# sch_easyeda.net
KiCad netlist of a schematic drawn in EasyEDA
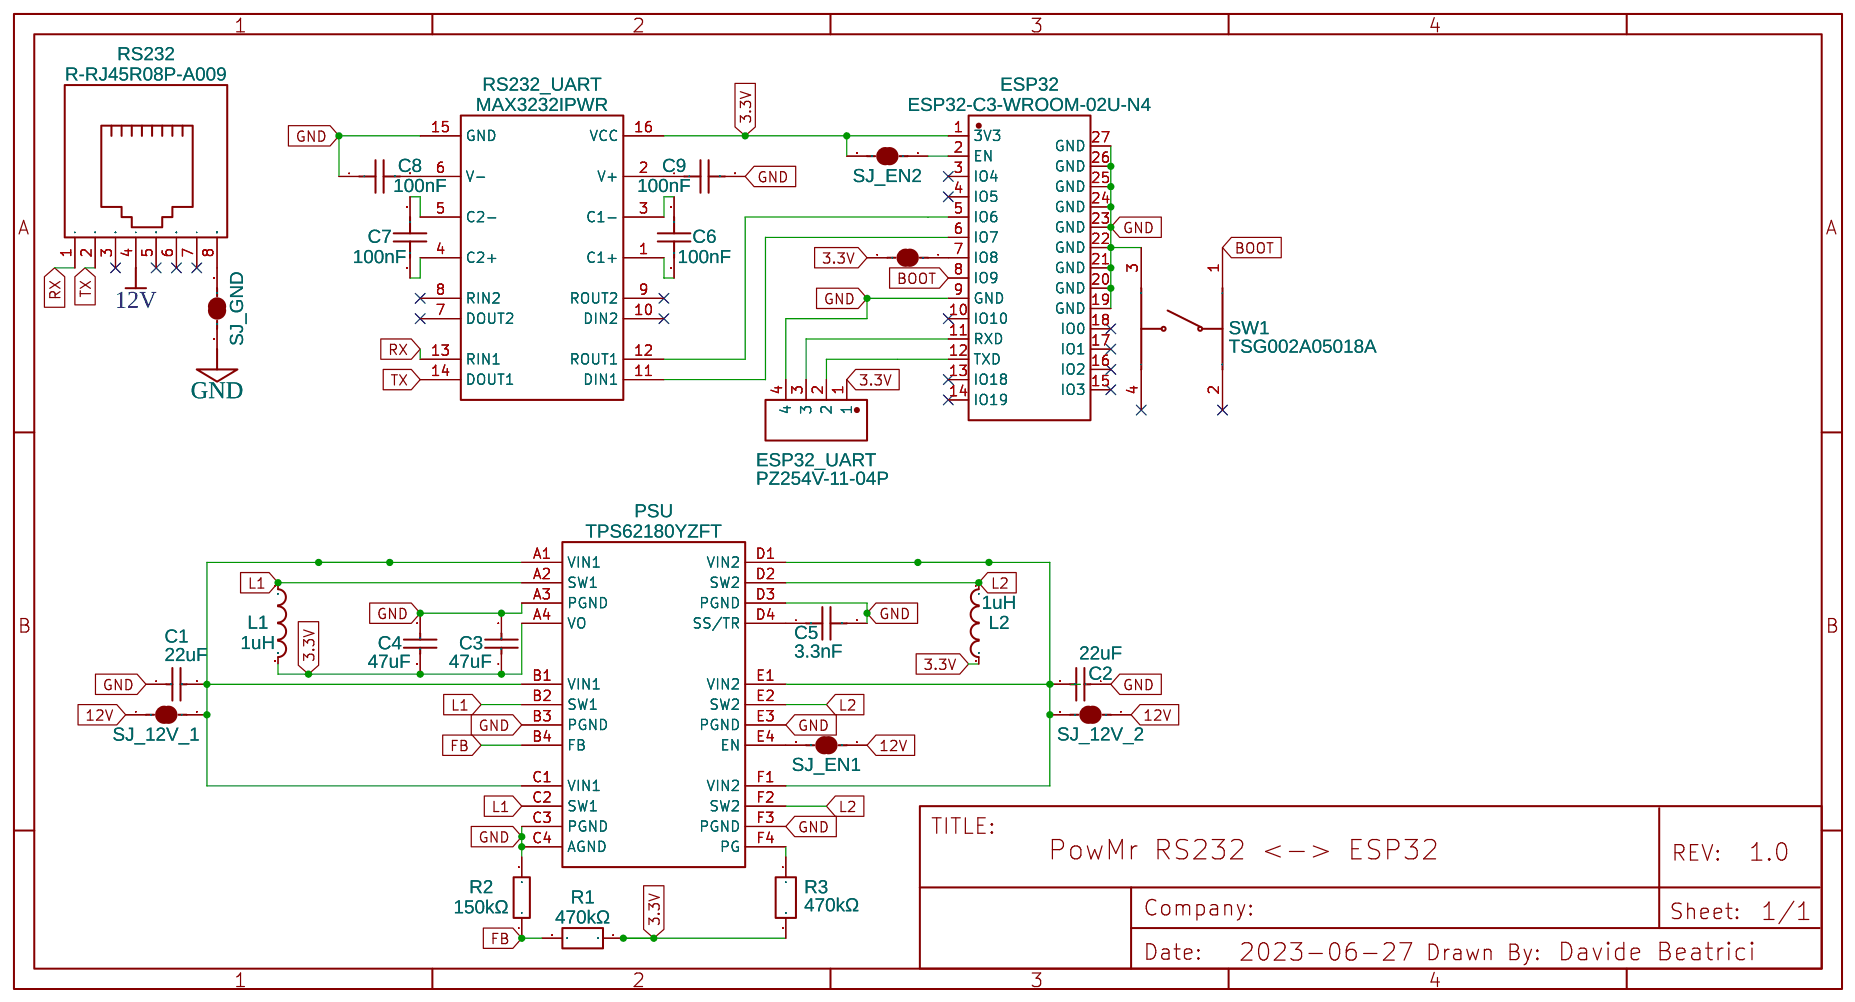
[diagram p0: schematic sheet]

(export (version "E")
  (design (tool "Eeschema 10.0.6"))
  (components
    (comp (ref "C1")
      (value "22uF")
      (fields
        (field (name "BOM_Manufacturer Part") "GRM21BR61E226ME44L")
        (field (name "BOM_Supplier Part") "C86816")
      )
      (libsource (lib "") (part "GRM21BR61E226ME44L"))
    )
    (comp (ref "C2")
      (value "22uF")
      (fields
        (field (name "BOM_Manufacturer Part") "GRM21BR61E226ME44L")
        (field (name "BOM_Supplier Part") "C86816")
      )
      (libsource (lib "") (part "GRM21BR61E226ME44L_1"))
    )
    (comp (ref "C3")
      (value "47uF")
      (fields
        (field (name "BOM_Manufacturer Part") "GRM21BR60J476ME15L")
        (field (name "BOM_Supplier Part") "C77072")
      )
      (libsource (lib "") (part "GRM21BR60J476ME15L"))
    )
    (comp (ref "C4")
      (value "47uF")
      (fields
        (field (name "BOM_Manufacturer Part") "GRM21BR60J476ME15L")
        (field (name "BOM_Supplier Part") "C77072")
      )
      (libsource (lib "") (part "GRM21BR60J476ME15L"))
    )
    (comp (ref "C5")
      (value "3.3nF")
      (fields
        (field (name "BOM_Manufacturer Part") "GRM155R71H332KA01D")
        (field (name "BOM_Supplier Part") "C85963")
      )
      (libsource (lib "") (part "GRM155R71H332KA01D"))
    )
    (comp (ref "C6")
      (value "100nF")
      (fields
        (field (name "BOM_Manufacturer Part") "GRM155R71C104KA88D")
        (field (name "BOM_Supplier Part") "C71629")
      )
      (libsource (lib "") (part "GRM155R71C104KA88D_1"))
    )
    (comp (ref "C7")
      (value "100nF")
      (fields
        (field (name "BOM_Manufacturer Part") "GRM155R71C104KA88D")
        (field (name "BOM_Supplier Part") "C71629")
      )
      (libsource (lib "") (part "GRM155R71C104KA88D_1"))
    )
    (comp (ref "C8")
      (value "100nF")
      (fields
        (field (name "BOM_Manufacturer Part") "GRM155R71C104KA88D")
        (field (name "BOM_Supplier Part") "C71629")
      )
      (libsource (lib "") (part "GRM155R71C104KA88D"))
    )
    (comp (ref "C9")
      (value "100nF")
      (fields
        (field (name "BOM_Manufacturer Part") "GRM155R71C104KA88D")
        (field (name "BOM_Supplier Part") "C71629")
      )
      (libsource (lib "") (part "GRM155R71C104KA88D"))
    )
    (comp (ref "ESP32")
      (value "ESP32-C3-WROOM-02U-N4")
      (fields (field (name "BOM_Supplier Part") "C2926676"))
      (libsource (lib "") (part "ESP32-C3-WROOM-02U-N4"))
    )
    (comp (ref "ESP32_UART")
      (value "PZ254V-11-04P")
      (fields (field (name "BOM_Supplier Part") "C492403"))
      (libsource (lib "") (part "PZ254V-11-04P"))
    )
    (comp (ref "L1")
      (value "1uH")
      (fields
        (field (name "BOM_Manufacturer Part") "DFE252012F-1R0M=P2")
        (field (name "BOM_Supplier Part") "C435392")
      )
      (libsource (lib "") (part "DFE252012F-1R0M=P2_1"))
    )
    (comp (ref "L2")
      (value "1uH")
      (fields
        (field (name "BOM_Manufacturer Part") "DFE252012F-1R0M=P2")
        (field (name "BOM_Supplier Part") "C435392")
      )
      (libsource (lib "") (part "DFE252012F-1R0M=P2"))
    )
    (comp (ref "PSU")
      (value "TPS62180YZFT")
      (fields (field (name "BOM_Supplier Part") "C73980"))
      (libsource (lib "") (part "TPS62180YZFT"))
    )
    (comp (ref "R1")
      (value "470kΩ")
      (fields
        (field (name "BOM_Manufacturer Part") "CRCW0402470KFKED")
        (field (name "BOM_Supplier Part") "C482181")
      )
      (libsource (lib "") (part "CRCW0402470KFKED"))
    )
    (comp (ref "R2")
      (value "150kΩ")
      (fields
        (field (name "BOM_Manufacturer Part") "0402WGF1503TCE")
        (field (name "BOM_Supplier Part") "C25755")
      )
      (libsource (lib "") (part "0402WGF1503TCE"))
    )
    (comp (ref "R3")
      (value "470kΩ")
      (fields
        (field (name "BOM_Manufacturer Part") "CRCW0402470KFKED")
        (field (name "BOM_Supplier Part") "C482181")
      )
      (libsource (lib "") (part "CRCW0402470KFKED_1"))
    )
    (comp (ref "RS232")
      (value "R-RJ45R08P-A009")
      (fields (field (name "BOM_Supplier Part") "C2902700"))
      (libsource (lib "") (part "R-RJ45R08P-A009"))
    )
    (comp (ref "RS232_UART")
      (value "MAX3232IPWR")
      (fields (field (name "BOM_Supplier Part") "C113205"))
      (libsource (lib "") (part "MAX3232IPWR"))
    )
    (comp (ref "SJ_12V_1") (value "SJ_12V_1") (libsource (lib "") (part "SOLDERJUMPERNC2_3")))
    (comp (ref "SJ_12V_2") (value "SJ_12V_2") (libsource (lib "") (part "SOLDERJUMPERNC2_2")))
    (comp (ref "SJ_EN1") (value "SJ_EN1") (libsource (lib "") (part "SOLDERJUMPERNC2_1")))
    (comp (ref "SJ_EN2") (value "SJ_EN2") (libsource (lib "") (part "SOLDERJUMPERNC2_1")))
    (comp (ref "SJ_GND") (value "SJ_GND") (libsource (lib "") (part "SOLDERJUMPERNC2_4")))
    (comp (ref "SJ_IO8") (value "SJ_IO8") (libsource (lib "") (part "SOLDERJUMPERNC2")))
    (comp (ref "SW1")
      (value "TSG002A05018A")
      (fields (field (name "BOM_Supplier Part") "C2888616"))
      (libsource (lib "") (part "TSG002A05018A"))
    )
  )
  (nets
    (net (code "1") (name "3.3V") (class "Default")
      (node (ref "C3") (pin "1") (pinfunction "1_1") (pintype "input"))
      (node (ref "C4") (pin "1") (pinfunction "1_1") (pintype "input"))
      (node (ref "ESP32") (pin "1") (pinfunction "3V3_1") (pintype "unspecified"))
      (node (ref "ESP32_UART") (pin "1") (pinfunction "1_1") (pintype "unspecified"))
      (node (ref "L1") (pin "2") (pinfunction "2_2") (pintype "unspecified"))
      (node (ref "L2") (pin "2") (pinfunction "2_2") (pintype "unspecified"))
      (node (ref "PSU") (pin "A4") (pinfunction "VO_A4") (pintype "unspecified"))
      (node (ref "R1") (pin "1") (pinfunction "1_1") (pintype "unspecified"))
      (node (ref "R3") (pin "2") (pinfunction "2_2") (pintype "unspecified"))
      (node (ref "RS232_UART") (pin "16") (pinfunction "VCC_16") (pintype "passive"))
      (node (ref "SJ_EN2") (pin "2") (pinfunction "2_2") (pintype "unspecified"))
      (node (ref "SJ_IO8") (pin "2") (pinfunction "2_2") (pintype "unspecified"))
    )
    (net (code "2") (name "12V") (class "Default")
      (node (ref "RS232") (pin "4") (pinfunction "4_4") (pintype "unspecified"))
      (node (ref "SJ_12V_1") (pin "1") (pinfunction "1_1") (pintype "unspecified"))
      (node (ref "SJ_12V_2") (pin "1") (pinfunction "1_1") (pintype "unspecified"))
      (node (ref "SJ_EN1") (pin "1") (pinfunction "1_1") (pintype "unspecified"))
    )
    (net (code "3") (name "BOOT") (class "Default")
      (node (ref "ESP32") (pin "8") (pinfunction "IO9_8") (pintype "unspecified"))
      (node (ref "SW1") (pin "1") (pinfunction "1_1") (pintype "unspecified"))
    )
    (net (code "4") (name "FB") (class "Default")
      (node (ref "PSU") (pin "B4") (pinfunction "FB_B4") (pintype "unspecified"))
      (node (ref "R1") (pin "2") (pinfunction "2_2") (pintype "unspecified"))
      (node (ref "R2") (pin "1") (pinfunction "1_1") (pintype "input"))
    )
    (net (code "5") (name "GND") (class "Default")
      (node (ref "C1") (pin "1") (pinfunction "1_1") (pintype "input"))
      (node (ref "C2") (pin "1") (pinfunction "1_1") (pintype "input"))
      (node (ref "C3") (pin "2") (pinfunction "2_2") (pintype "input"))
      (node (ref "C4") (pin "2") (pinfunction "2_2") (pintype "input"))
      (node (ref "C5") (pin "2") (pinfunction "2_2") (pintype "unspecified"))
      (node (ref "C8") (pin "1") (pinfunction "1_1") (pintype "unspecified"))
      (node (ref "C9") (pin "2") (pinfunction "2_2") (pintype "unspecified"))
      (node (ref "ESP32") (pin "19") (pinfunction "GND_19") (pintype "unspecified"))
      (node (ref "ESP32") (pin "20") (pinfunction "GND_20") (pintype "unspecified"))
      (node (ref "ESP32") (pin "21") (pinfunction "GND_21") (pintype "unspecified"))
      (node (ref "ESP32") (pin "22") (pinfunction "GND_22") (pintype "unspecified"))
      (node (ref "ESP32") (pin "23") (pinfunction "GND_23") (pintype "unspecified"))
      (node (ref "ESP32") (pin "24") (pinfunction "GND_24") (pintype "unspecified"))
      (node (ref "ESP32") (pin "25") (pinfunction "GND_25") (pintype "unspecified"))
      (node (ref "ESP32") (pin "26") (pinfunction "GND_26") (pintype "unspecified"))
      (node (ref "ESP32") (pin "27") (pinfunction "GND_27") (pintype "unspecified"))
      (node (ref "ESP32") (pin "9") (pinfunction "GND_9") (pintype "unspecified"))
      (node (ref "ESP32_UART") (pin "4") (pinfunction "4_4") (pintype "unspecified"))
      (node (ref "PSU") (pin "A3") (pinfunction "PGND_A3") (pintype "unspecified"))
      (node (ref "PSU") (pin "B3") (pinfunction "PGND_B3") (pintype "unspecified"))
      (node (ref "PSU") (pin "C3") (pinfunction "PGND_C3") (pintype "unspecified"))
      (node (ref "PSU") (pin "C4") (pinfunction "AGND_C4") (pintype "unspecified"))
      (node (ref "PSU") (pin "D3") (pinfunction "PGND_D3") (pintype "unspecified"))
      (node (ref "PSU") (pin "E3") (pinfunction "PGND_E3") (pintype "unspecified"))
      (node (ref "PSU") (pin "F3") (pinfunction "PGND_F3") (pintype "unspecified"))
      (node (ref "R2") (pin "2") (pinfunction "2_2") (pintype "input"))
      (node (ref "RS232_UART") (pin "15") (pinfunction "GND_15") (pintype "passive"))
      (node (ref "SJ_GND") (pin "1") (pinfunction "1_1") (pintype "unspecified"))
      (node (ref "SW1") (pin "3") (pinfunction "3_3") (pintype "unspecified"))
    )
    (net (code "6") (name "L1") (class "Default")
      (node (ref "L1") (pin "1") (pinfunction "1_1") (pintype "unspecified"))
      (node (ref "PSU") (pin "A2") (pinfunction "SW1_A2") (pintype "unspecified"))
      (node (ref "PSU") (pin "B2") (pinfunction "SW1_B2") (pintype "unspecified"))
      (node (ref "PSU") (pin "C2") (pinfunction "SW1_C2") (pintype "unspecified"))
    )
    (net (code "7") (name "L2") (class "Default")
      (node (ref "L2") (pin "1") (pinfunction "1_1") (pintype "unspecified"))
      (node (ref "PSU") (pin "D2") (pinfunction "SW2_D2") (pintype "unspecified"))
      (node (ref "PSU") (pin "E2") (pinfunction "SW2_E2") (pintype "unspecified"))
      (node (ref "PSU") (pin "F2") (pinfunction "SW2_F2") (pintype "unspecified"))
    )
    (net (code "8") (name "Net-(C1-Pad2)") (class "Default")
      (node (ref "C1") (pin "2") (pinfunction "2_2") (pintype "input"))
      (node (ref "PSU") (pin "A1") (pinfunction "VIN1_A1") (pintype "unspecified"))
      (node (ref "PSU") (pin "B1") (pinfunction "VIN1_B1") (pintype "unspecified"))
      (node (ref "PSU") (pin "C1") (pinfunction "VIN1_C1") (pintype "unspecified"))
      (node (ref "SJ_12V_1") (pin "2") (pinfunction "2_2") (pintype "unspecified"))
    )
    (net (code "9") (name "Net-(C2-Pad2)") (class "Default")
      (node (ref "C2") (pin "2") (pinfunction "2_2") (pintype "input"))
      (node (ref "PSU") (pin "D1") (pinfunction "VIN2_D1") (pintype "unspecified"))
      (node (ref "PSU") (pin "E1") (pinfunction "VIN2_E1") (pintype "unspecified"))
      (node (ref "PSU") (pin "F1") (pinfunction "VIN2_F1") (pintype "unspecified"))
      (node (ref "SJ_12V_2") (pin "2") (pinfunction "2_2") (pintype "unspecified"))
    )
    (net (code "10") (name "Net-(ESP32-EN)") (class "Default")
      (node (ref "ESP32") (pin "2") (pinfunction "EN_2") (pintype "unspecified"))
      (node (ref "SJ_EN2") (pin "1") (pinfunction "1_1") (pintype "unspecified"))
    )
    (net (code "11") (name "Net-(ESP32-IO6)") (class "Default")
      (node (ref "ESP32") (pin "5") (pinfunction "IO6_5") (pintype "unspecified"))
      (node (ref "RS232_UART") (pin "12") (pinfunction "ROUT1_12") (pintype "output"))
    )
    (net (code "12") (name "Net-(ESP32-IO7)") (class "Default")
      (node (ref "ESP32") (pin "6") (pinfunction "IO7_6") (pintype "unspecified"))
      (node (ref "RS232_UART") (pin "11") (pinfunction "DIN1_11") (pintype "unspecified"))
    )
    (net (code "13") (name "Net-(ESP32-IO8)") (class "Default")
      (node (ref "ESP32") (pin "7") (pinfunction "IO8_7") (pintype "unspecified"))
      (node (ref "SJ_IO8") (pin "1") (pinfunction "1_1") (pintype "unspecified"))
    )
    (net (code "14") (name "Net-(ESP32-RXD)") (class "Default")
      (node (ref "ESP32") (pin "11") (pinfunction "RXD_11") (pintype "unspecified"))
      (node (ref "ESP32_UART") (pin "3") (pinfunction "3_3") (pintype "unspecified"))
    )
    (net (code "15") (name "Net-(ESP32-TXD)") (class "Default")
      (node (ref "ESP32") (pin "12") (pinfunction "TXD_12") (pintype "unspecified"))
      (node (ref "ESP32_UART") (pin "2") (pinfunction "2_2") (pintype "unspecified"))
    )
    (net (code "16") (name "Net-(PSU-EN)") (class "Default")
      (node (ref "PSU") (pin "E4") (pinfunction "EN_E4") (pintype "unspecified"))
      (node (ref "SJ_EN1") (pin "2") (pinfunction "2_2") (pintype "unspecified"))
    )
    (net (code "17") (name "Net-(PSU-PG)") (class "Default")
      (node (ref "PSU") (pin "F4") (pinfunction "PG_F4") (pintype "unspecified"))
      (node (ref "R3") (pin "1") (pinfunction "1_1") (pintype "unspecified"))
    )
    (net (code "18") (name "Net-(PSU-SS{slash}TR)") (class "Default")
      (node (ref "C5") (pin "1") (pinfunction "1_1") (pintype "unspecified"))
      (node (ref "PSU") (pin "D4") (pinfunction "SS/TR_D4") (pintype "unspecified"))
    )
    (net (code "19") (name "Net-(RS232-Pad8)") (class "Default")
      (node (ref "RS232") (pin "8") (pinfunction "8_8") (pintype "unspecified"))
      (node (ref "SJ_GND") (pin "2") (pinfunction "2_2") (pintype "unspecified"))
    )
    (net (code "20") (name "Net-(RS232_UART-C1+)") (class "Default")
      (node (ref "C6") (pin "1") (pinfunction "1_1") (pintype "unspecified"))
      (node (ref "RS232_UART") (pin "1") (pinfunction "C1+_1") (pintype "unspecified"))
    )
    (net (code "21") (name "Net-(RS232_UART-C1-)") (class "Default")
      (node (ref "C6") (pin "2") (pinfunction "2_2") (pintype "unspecified"))
      (node (ref "RS232_UART") (pin "3") (pinfunction "C1-_3") (pintype "unspecified"))
    )
    (net (code "22") (name "Net-(RS232_UART-C2+)") (class "Default")
      (node (ref "C7") (pin "1") (pinfunction "1_1") (pintype "unspecified"))
      (node (ref "RS232_UART") (pin "4") (pinfunction "C2+_4") (pintype "unspecified"))
    )
    (net (code "23") (name "Net-(RS232_UART-C2-)") (class "Default")
      (node (ref "C7") (pin "2") (pinfunction "2_2") (pintype "unspecified"))
      (node (ref "RS232_UART") (pin "5") (pinfunction "C2-_5") (pintype "unspecified"))
    )
    (net (code "24") (name "Net-(RS232_UART-V+)") (class "Default")
      (node (ref "C9") (pin "1") (pinfunction "1_1") (pintype "unspecified"))
      (node (ref "RS232_UART") (pin "2") (pinfunction "V+_2") (pintype "passive"))
    )
    (net (code "25") (name "Net-(RS232_UART-V-)") (class "Default")
      (node (ref "C8") (pin "2") (pinfunction "2_2") (pintype "unspecified"))
      (node (ref "RS232_UART") (pin "6") (pinfunction "V-_6") (pintype "passive"))
    )
    (net (code "26") (name "RX") (class "Default")
      (node (ref "RS232") (pin "1") (pinfunction "1_1") (pintype "unspecified"))
      (node (ref "RS232_UART") (pin "13") (pinfunction "RIN1_13") (pintype "unspecified"))
    )
    (net (code "27") (name "TX") (class "Default")
      (node (ref "RS232") (pin "2") (pinfunction "2_2") (pintype "unspecified"))
      (node (ref "RS232_UART") (pin "14") (pinfunction "DOUT1_14") (pintype "output"))
    )
    (net (code "28") (name "unconnected-(ESP32-IO0-Pad18)") (class "Default")
      (node (ref "ESP32") (pin "18") (pinfunction "IO0_18") (pintype "unspecified+no_connect"))
    )
    (net (code "29") (name "unconnected-(ESP32-IO1-Pad17)") (class "Default")
      (node (ref "ESP32") (pin "17") (pinfunction "IO1_17") (pintype "unspecified+no_connect"))
    )
    (net (code "30") (name "unconnected-(ESP32-IO2-Pad16)") (class "Default")
      (node (ref "ESP32") (pin "16") (pinfunction "IO2_16") (pintype "unspecified+no_connect"))
    )
    (net (code "31") (name "unconnected-(ESP32-IO3-Pad15)") (class "Default")
      (node (ref "ESP32") (pin "15") (pinfunction "IO3_15") (pintype "unspecified+no_connect"))
    )
    (net (code "32") (name "unconnected-(ESP32-IO4-Pad3)") (class "Default")
      (node (ref "ESP32") (pin "3") (pinfunction "IO4_3") (pintype "unspecified+no_connect"))
    )
    (net (code "33") (name "unconnected-(ESP32-IO5-Pad4)") (class "Default")
      (node (ref "ESP32") (pin "4") (pinfunction "IO5_4") (pintype "unspecified+no_connect"))
    )
    (net (code "34") (name "unconnected-(ESP32-IO10-Pad10)") (class "Default")
      (node (ref "ESP32") (pin "10") (pinfunction "IO10_10") (pintype "unspecified+no_connect"))
    )
    (net (code "35") (name "unconnected-(ESP32-IO18-Pad13)") (class "Default")
      (node (ref "ESP32") (pin "13") (pinfunction "IO18_13") (pintype "unspecified+no_connect"))
    )
    (net (code "36") (name "unconnected-(ESP32-IO19-Pad14)") (class "Default")
      (node (ref "ESP32") (pin "14") (pinfunction "IO19_14") (pintype "unspecified+no_connect"))
    )
    (net (code "37") (name "unconnected-(RS232-Pad3)") (class "Default")
      (node (ref "RS232") (pin "3") (pinfunction "3_3") (pintype "unspecified+no_connect"))
    )
    (net (code "38") (name "unconnected-(RS232-Pad5)") (class "Default")
      (node (ref "RS232") (pin "5") (pinfunction "5_5") (pintype "unspecified+no_connect"))
    )
    (net (code "39") (name "unconnected-(RS232-Pad6)") (class "Default")
      (node (ref "RS232") (pin "6") (pinfunction "6_6") (pintype "unspecified+no_connect"))
    )
    (net (code "40") (name "unconnected-(RS232-Pad7)") (class "Default")
      (node (ref "RS232") (pin "7") (pinfunction "7_7") (pintype "unspecified+no_connect"))
    )
    (net (code "41") (name "unconnected-(RS232_UART-DIN2-Pad10)") (class "Default")
      (node (ref "RS232_UART") (pin "10") (pinfunction "DIN2_10") (pintype "unspecified+no_connect"))
    )
    (net (code "42") (name "unconnected-(RS232_UART-DOUT2-Pad7)") (class "Default")
      (node (ref "RS232_UART") (pin "7") (pinfunction "DOUT2_7") (pintype "output+no_connect"))
    )
    (net (code "43") (name "unconnected-(RS232_UART-RIN2-Pad8)") (class "Default")
      (node (ref "RS232_UART") (pin "8") (pinfunction "RIN2_8") (pintype "unspecified+no_connect"))
    )
    (net (code "44") (name "unconnected-(RS232_UART-ROUT2-Pad9)") (class "Default")
      (node (ref "RS232_UART") (pin "9") (pinfunction "ROUT2_9") (pintype "output+no_connect"))
    )
    (net (code "45") (name "unconnected-(SW1-Pad2)") (class "Default")
      (node (ref "SW1") (pin "2") (pinfunction "2_2") (pintype "unspecified+no_connect"))
    )
    (net (code "46") (name "unconnected-(SW1-Pad4)") (class "Default")
      (node (ref "SW1") (pin "4") (pinfunction "4_4") (pintype "unspecified+no_connect"))
    )
  )
)
